# nodemcu-tft144-radio.net
KiCad netlist of a schematic drawn in Altium Designer
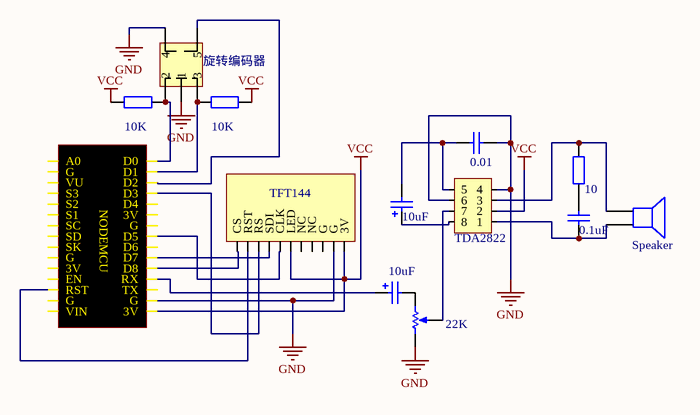
[diagram p0: nodemcu-tft144-radio.SchDoc]

(export (version "E")
  (design (tool "Eeschema 10.0.6"))
  (components
    (comp (ref "C1")
      (value "10uF")
      (footprint "POLAR0.8")
      (description "Polarized Capacitor (Axial)")
      (fields (field (name "Comment") "Cap Pol2") (field (name "PUBLISHER") "Altium Limited"))
      (libsource (lib "Miscellaneous Devices") (part "Cap Pol2"))
    )
    (comp (ref "C2")
      (value "10uF")
      (footprint "POLAR0.8")
      (description "Polarized Capacitor (Axial)")
      (fields (field (name "Comment") "Cap Pol2") (field (name "PUBLISHER") "Altium Limited"))
      (libsource (lib "Miscellaneous Devices") (part "Cap Pol2"))
    )
    (comp (ref "C3")
      (value "0.01")
      (footprint "RAD-0.3")
      (description "Capacitor")
      (fields (field (name "Comment") "Cap") (field (name "PUBLISHER") "Altium Limited"))
      (libsource (lib "Miscellaneous Devices") (part "Cap"))
    )
    (comp (ref "C4")
      (value "0.1uF")
      (footprint "RAD-0.3")
      (description "Capacitor")
      (fields (field (name "Comment") "Cap") (field (name "PUBLISHER") "Altium Limited"))
      (libsource (lib "Miscellaneous Devices") (part "Cap"))
    )
    (comp (ref "IC1") (value "TDA2822") (libsource (lib "shsInt_Lib") (part "TDA2822")))
    (comp (ref "LS1")
      (value "Speaker")
      (footprint "PIN2")
      (description "Loudspeaker")
      (fields (field (name "PUBLISHER") "Altium Limited"))
      (libsource (lib "Miscellaneous Devices") (part "Speaker"))
    )
    (comp (ref "nodemcu")
      (value "nodemcu")
      (footprint "NODEMCU")
      (libsource (lib "Integrated_Library1") (part "nodemcu"))
    )
    (comp (ref "R1")
      (value "22K")
      (footprint "VR5")
      (description "Potentiometer")
      (fields (field (name "Comment") "RPot") (field (name "PUBLISHER") "Altium Limited"))
      (libsource (lib "Miscellaneous Devices") (part "RPot"))
    )
    (comp (ref "R2")
      (value "10")
      (footprint "AXIAL-0.4")
      (description "Resistor")
      (fields (field (name "Comment") "Res2") (field (name "PUBLISHER") "Altium Limited"))
      (libsource (lib "Miscellaneous Devices") (part "Res2"))
    )
    (comp (ref "R6")
      (value "10K")
      (footprint "AXIAL-0.4")
      (description "Resistor")
      (fields (field (name "Comment") "Res2") (field (name "PUBLISHER") "Altium Limited"))
      (libsource (lib "") (part "Res2_2"))
    )
    (comp (ref "R7")
      (value "10K")
      (footprint "AXIAL-0.4")
      (description "Resistor")
      (fields (field (name "Comment") "Res2") (field (name "PUBLISHER") "Altium Limited"))
      (libsource (lib "") (part "Res2_1"))
    )
    (comp (ref "ro1")
      (value "旋转编码器")
      (footprint "rotate_switch")
      (libsource (lib "shsInt_Lib") (part "rotate_switch"))
    )
    (comp (ref "TFT144")
      (value "TFT144")
      (footprint "TFT144")
      (libsource (lib "Integrated_Library1") (part "TFT144"))
    )
  )
  (nets
    (net (code "1") (name "GND") (class "Default")
      (node (ref "C3") (pin "2") (pinfunction "2_2") (pintype "passive"))
      (node (ref "IC1") (pin "4") (pinfunction "4_4") (pintype "passive"))
      (node (ref "IC1") (pin "6") (pinfunction "6_6") (pintype "passive"))
      (node (ref "R1") (pin "1") (pinfunction "TOP_1") (pintype "passive"))
      (node (ref "TFT144") (pin "10") (pinfunction "G_10") (pintype "passive"))
      (node (ref "nodemcu") (pin "17") (pinfunction "G_17") (pintype "passive"))
      (node (ref "ro1") (pin "1") (pinfunction "1_1") (pintype "passive"))
      (node (ref "ro1") (pin "4") (pinfunction "4_4") (pintype "passive"))
    )
    (net (code "2") (name "Net-(C2-Pad1)") (class "Default")
      (node (ref "C2") (pin "1") (pinfunction "1_1") (pintype "passive"))
      (node (ref "IC1") (pin "8") (pinfunction "8_8") (pintype "passive"))
    )
    (net (code "3") (name "Net-(C2-Pad2)") (class "Default")
      (node (ref "C2") (pin "2") (pinfunction "2_2") (pintype "passive"))
      (node (ref "C3") (pin "1") (pinfunction "1_1") (pintype "passive"))
      (node (ref "IC1") (pin "5") (pinfunction "5_5") (pintype "passive"))
    )
    (net (code "4") (name "Net-(C4-Pad1)") (class "Default")
      (node (ref "C4") (pin "1") (pinfunction "1_1") (pintype "passive"))
      (node (ref "IC1") (pin "1") (pinfunction "1_1") (pintype "passive"))
      (node (ref "LS1") (pin "2") (pinfunction "2_2") (pintype "passive"))
    )
    (net (code "5") (name "Net-(C4-Pad2)") (class "Default")
      (node (ref "C4") (pin "2") (pinfunction "2_2") (pintype "passive"))
      (node (ref "R2") (pin "1") (pinfunction "1_1") (pintype "passive"))
    )
    (net (code "6") (name "Net-(IC1-Pad3)") (class "Default")
      (node (ref "IC1") (pin "3") (pinfunction "3_3") (pintype "passive"))
      (node (ref "LS1") (pin "1") (pinfunction "1_1") (pintype "passive"))
      (node (ref "R2") (pin "2") (pinfunction "2_2") (pintype "passive"))
    )
    (net (code "7") (name "Net-(R1-BOT)") (class "Default")
      (node (ref "C1") (pin "2") (pinfunction "2_2") (pintype "passive"))
      (node (ref "R1") (pin "2") (pinfunction "BOT_2") (pintype "passive"))
    )
    (net (code "8") (name "Net-(R1-TAP)") (class "Default")
      (node (ref "IC1") (pin "7") (pinfunction "7_7") (pintype "passive"))
      (node (ref "R1") (pin "3") (pinfunction "TAP_3") (pintype "passive"))
    )
    (net (code "9") (name "Net-(TFT144-CLK)") (class "Default")
      (node (ref "TFT144") (pin "5") (pinfunction "CLK_5") (pintype "passive"))
      (node (ref "nodemcu") (pin "23") (pinfunction "D5_23") (pintype "passive"))
    )
    (net (code "10") (name "Net-(TFT144-CS)") (class "Default")
      (node (ref "TFT144") (pin "1") (pinfunction "CS_1") (pintype "passive"))
      (node (ref "nodemcu") (pin "20") (pinfunction "D8_20") (pintype "passive"))
    )
    (net (code "11") (name "Net-(TFT144-RS)") (class "Default")
      (node (ref "TFT144") (pin "3") (pinfunction "RS_3") (pintype "passive"))
      (node (ref "nodemcu") (pin "27") (pinfunction "D3_27") (pintype "passive"))
    )
    (net (code "12") (name "Net-(TFT144-RST)") (class "Default")
      (node (ref "TFT144") (pin "2") (pinfunction "RST_2") (pintype "passive"))
      (node (ref "nodemcu") (pin "13") (pinfunction "RST_13") (pintype "passive"))
    )
    (net (code "13") (name "Net-(TFT144-SDI)") (class "Default")
      (node (ref "TFT144") (pin "4") (pinfunction "SDI_4") (pintype "passive"))
      (node (ref "nodemcu") (pin "21") (pinfunction "D7_21") (pintype "passive"))
    )
    (net (code "14") (name "Net-(nodemcu-D0)") (class "Default")
      (node (ref "R6") (pin "1") (pinfunction "1_1") (pintype "passive"))
      (node (ref "nodemcu") (pin "30") (pinfunction "D0_30") (pintype "passive"))
      (node (ref "ro1") (pin "2") (pinfunction "2_2") (pintype "passive"))
    )
    (net (code "15") (name "Net-(nodemcu-D1)") (class "Default")
      (node (ref "R7") (pin "1") (pinfunction "1_1") (pintype "passive"))
      (node (ref "nodemcu") (pin "29") (pinfunction "D1_29") (pintype "passive"))
      (node (ref "ro1") (pin "3") (pinfunction "3_3") (pintype "passive"))
    )
    (net (code "16") (name "Net-(nodemcu-D2)") (class "Default")
      (node (ref "nodemcu") (pin "28") (pinfunction "D2_28") (pintype "passive"))
      (node (ref "ro1") (pin "5") (pinfunction "5_5") (pintype "passive"))
    )
    (net (code "17") (name "Net-(nodemcu-RX)") (class "Default")
      (node (ref "C1") (pin "1") (pinfunction "1_1") (pintype "passive"))
      (node (ref "nodemcu") (pin "19") (pinfunction "RX_19") (pintype "passive"))
    )
    (net (code "18") (name "VCC") (class "Default")
      (node (ref "IC1") (pin "2") (pinfunction "2_2") (pintype "passive"))
      (node (ref "R6") (pin "2") (pinfunction "2_2") (pintype "passive"))
      (node (ref "R7") (pin "2") (pinfunction "2_2") (pintype "passive"))
      (node (ref "TFT144") (pin "11") (pinfunction "3V_11") (pintype "passive"))
      (node (ref "TFT144") (pin "6") (pinfunction "LED_6") (pintype "passive"))
      (node (ref "nodemcu") (pin "16") (pinfunction "3V_16") (pintype "passive"))
    )
    (net (code "19") (name "unconnected-(TFT144-G-Pad9)") (class "Default")
      (node (ref "TFT144") (pin "9") (pinfunction "G_9") (pintype "passive"))
    )
    (net (code "20") (name "unconnected-(TFT144-NC-Pad7)") (class "Default")
      (node (ref "TFT144") (pin "7") (pinfunction "NC_7") (pintype "passive"))
    )
    (net (code "21") (name "unconnected-(TFT144-NC-Pad8)") (class "Default")
      (node (ref "TFT144") (pin "8") (pinfunction "NC_8") (pintype "passive"))
    )
    (net (code "22") (name "unconnected-(nodemcu-3V-Pad11)") (class "Default")
      (node (ref "nodemcu") (pin "11") (pinfunction "3V_11") (pintype "passive"))
    )
    (net (code "23") (name "unconnected-(nodemcu-3V-Pad25)") (class "Default")
      (node (ref "nodemcu") (pin "25") (pinfunction "3V_25") (pintype "passive"))
    )
    (net (code "24") (name "unconnected-(nodemcu-A0-Pad1)") (class "Default")
      (node (ref "nodemcu") (pin "1") (pinfunction "A0_1") (pintype "passive"))
    )
    (net (code "25") (name "unconnected-(nodemcu-D4-Pad26)") (class "Default")
      (node (ref "nodemcu") (pin "26") (pinfunction "D4_26") (pintype "passive"))
    )
    (net (code "26") (name "unconnected-(nodemcu-D6-Pad22)") (class "Default")
      (node (ref "nodemcu") (pin "22") (pinfunction "D6_22") (pintype "passive"))
    )
    (net (code "27") (name "unconnected-(nodemcu-EN-Pad12)") (class "Default")
      (node (ref "nodemcu") (pin "12") (pinfunction "EN_12") (pintype "passive"))
    )
    (net (code "28") (name "unconnected-(nodemcu-G-Pad2)") (class "Default")
      (node (ref "nodemcu") (pin "2") (pinfunction "G_2") (pintype "passive"))
    )
    (net (code "29") (name "unconnected-(nodemcu-G-Pad10)") (class "Default")
      (node (ref "nodemcu") (pin "10") (pinfunction "G_10") (pintype "passive"))
    )
    (net (code "30") (name "unconnected-(nodemcu-G-Pad14)") (class "Default")
      (node (ref "nodemcu") (pin "14") (pinfunction "G_14") (pintype "passive"))
    )
    (net (code "31") (name "unconnected-(nodemcu-G-Pad24)") (class "Default")
      (node (ref "nodemcu") (pin "24") (pinfunction "G_24") (pintype "passive"))
    )
    (net (code "32") (name "unconnected-(nodemcu-S1-Pad6)") (class "Default")
      (node (ref "nodemcu") (pin "6") (pinfunction "S1_6") (pintype "passive"))
    )
    (net (code "33") (name "unconnected-(nodemcu-S2-Pad5)") (class "Default")
      (node (ref "nodemcu") (pin "5") (pinfunction "S2_5") (pintype "passive"))
    )
    (net (code "34") (name "unconnected-(nodemcu-S3-Pad4)") (class "Default")
      (node (ref "nodemcu") (pin "4") (pinfunction "S3_4") (pintype "passive"))
    )
    (net (code "35") (name "unconnected-(nodemcu-SC-Pad7)") (class "Default")
      (node (ref "nodemcu") (pin "7") (pinfunction "SC_7") (pintype "passive"))
    )
    (net (code "36") (name "unconnected-(nodemcu-SD-Pad8)") (class "Default")
      (node (ref "nodemcu") (pin "8") (pinfunction "SD_8") (pintype "passive"))
    )
    (net (code "37") (name "unconnected-(nodemcu-SK-Pad9)") (class "Default")
      (node (ref "nodemcu") (pin "9") (pinfunction "SK_9") (pintype "passive"))
    )
    (net (code "38") (name "unconnected-(nodemcu-TX-Pad18)") (class "Default")
      (node (ref "nodemcu") (pin "18") (pinfunction "TX_18") (pintype "passive"))
    )
    (net (code "39") (name "unconnected-(nodemcu-VIN-Pad15)") (class "Default")
      (node (ref "nodemcu") (pin "15") (pinfunction "VIN_15") (pintype "passive"))
    )
    (net (code "40") (name "unconnected-(nodemcu-VU-Pad3)") (class "Default")
      (node (ref "nodemcu") (pin "3") (pinfunction "VU_3") (pintype "passive"))
    )
  )
)
